# 1-Schematic_simple_slew_limiter.net
KiCad netlist of a schematic drawn in EasyEDA
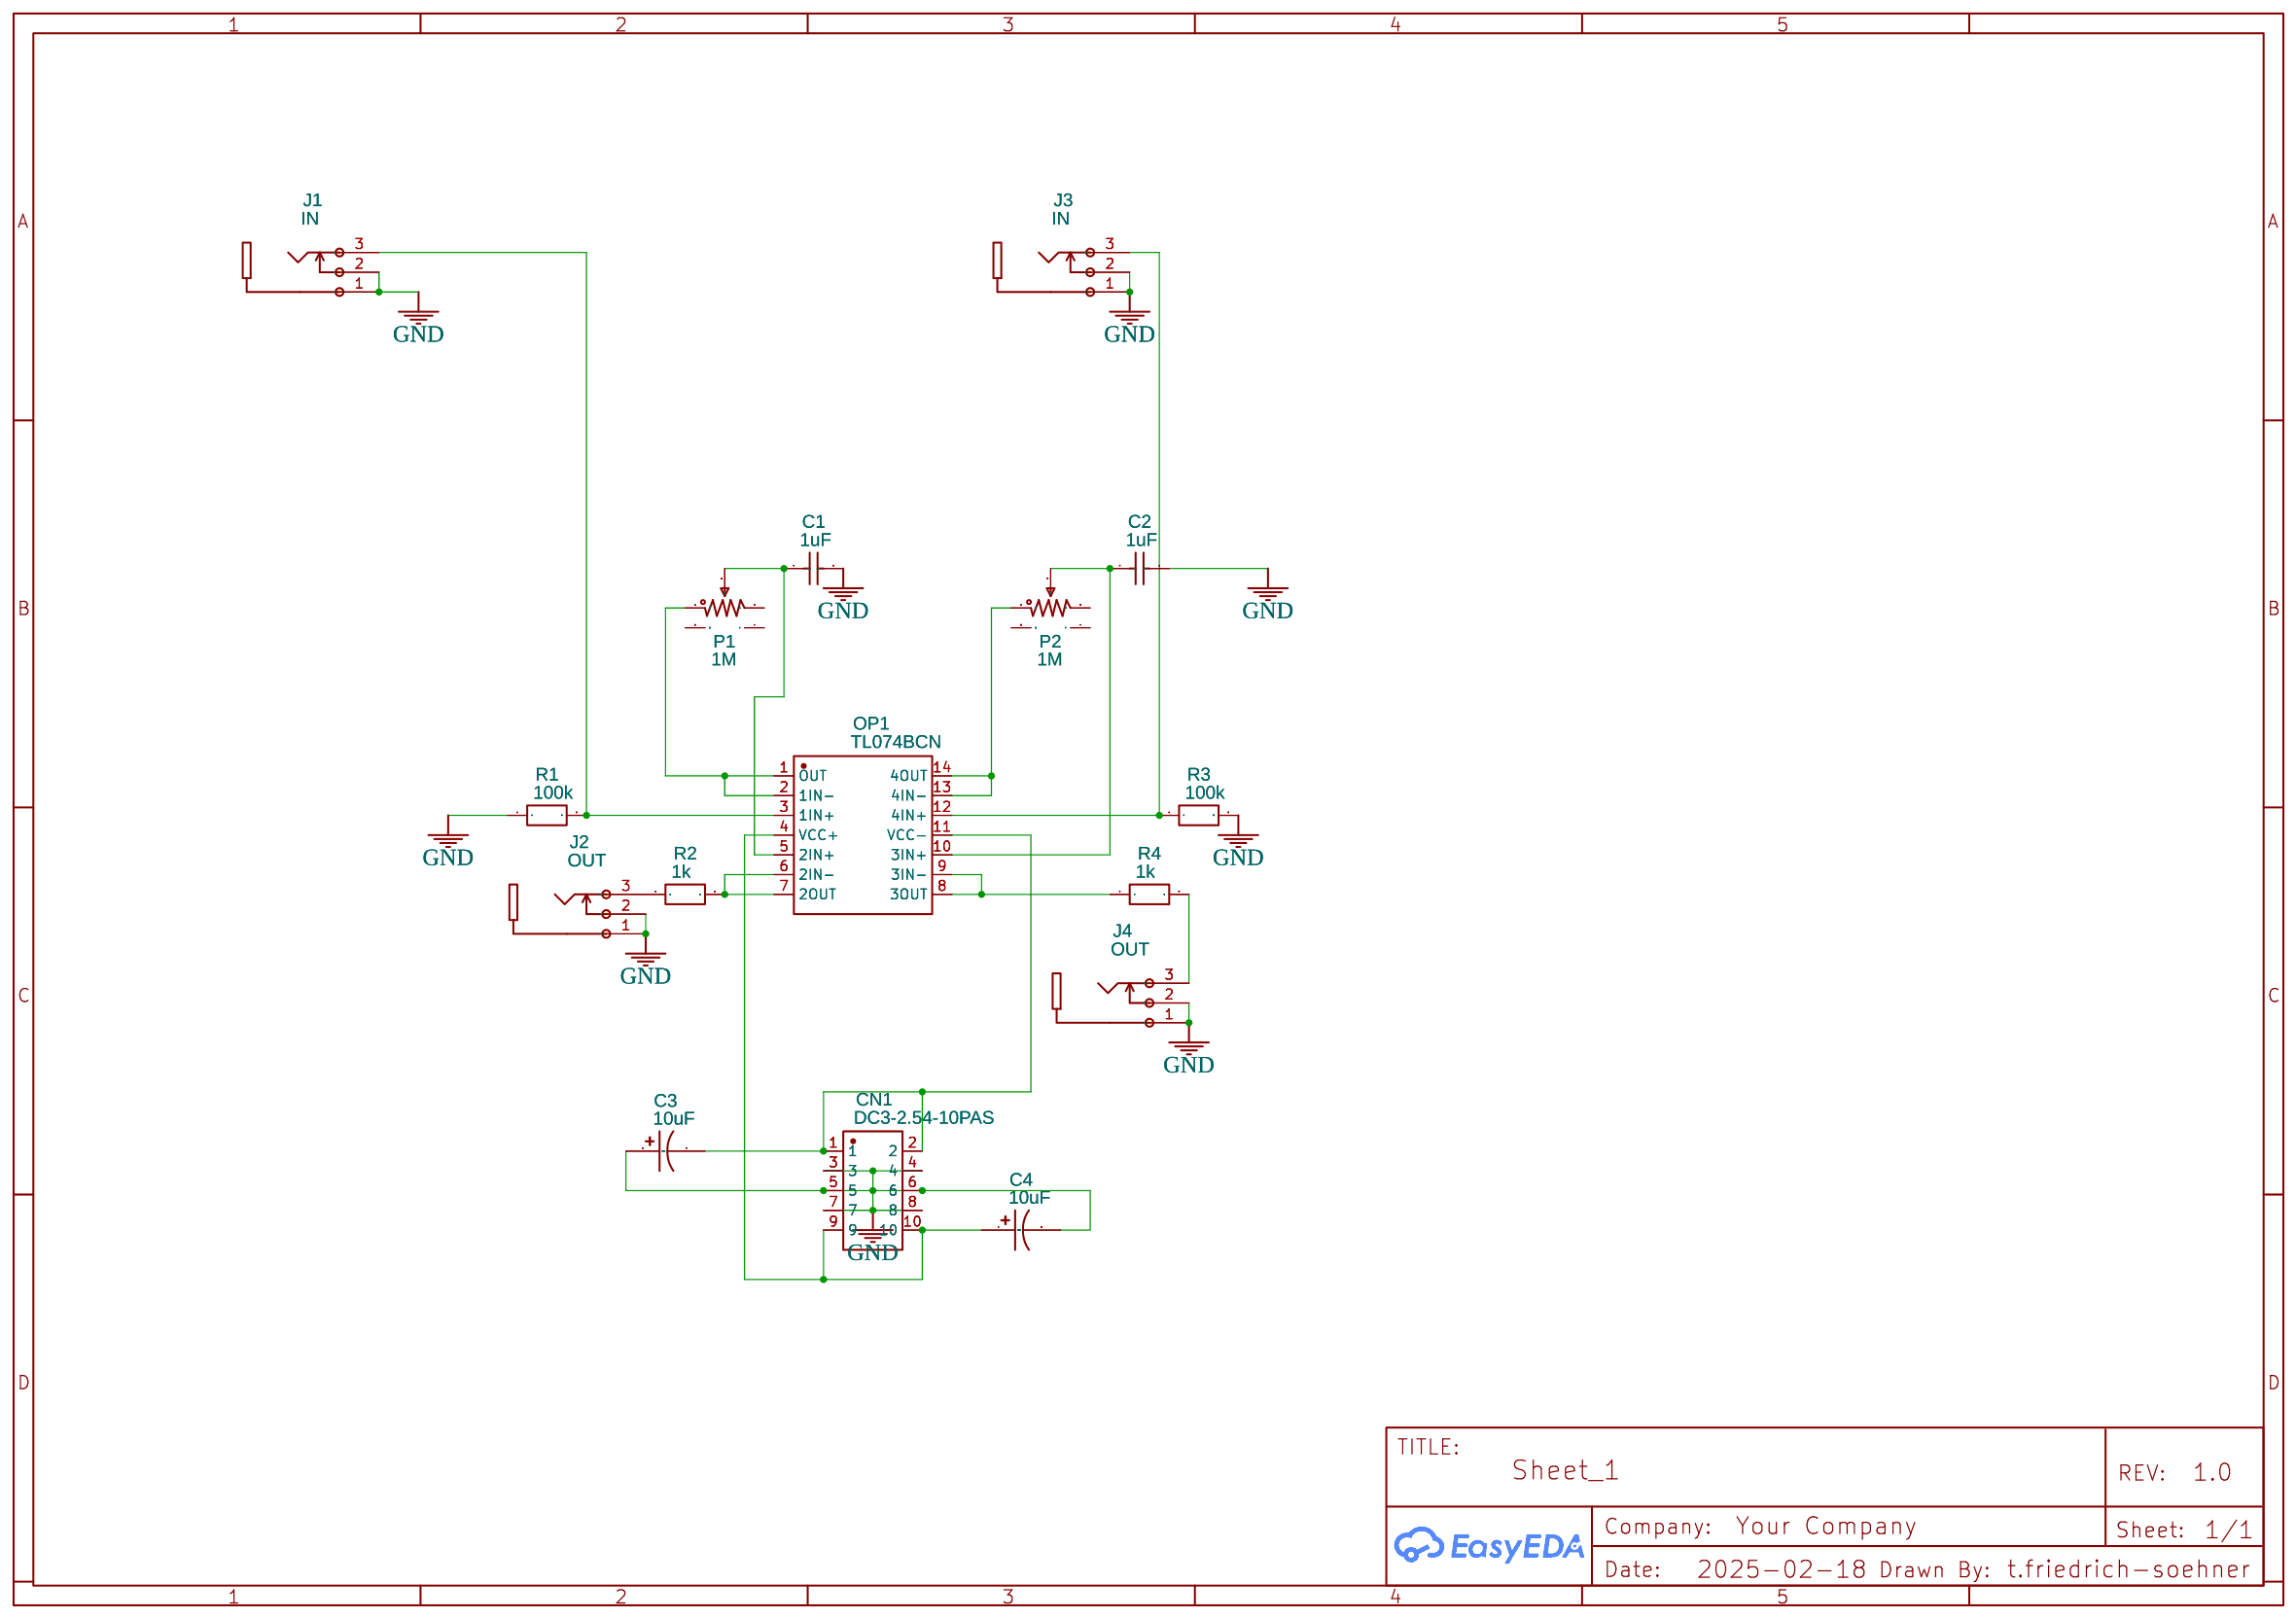
[diagram p0: schematic sheet]

(export (version "E")
  (design (tool "Eeschema 10.0.6"))
  (components
    (comp (ref "C1")
      (value "1uF")
      (fields
        (field (name "Manufacturer Part") "0.22uF 5% 100VCalibration capacitor")
        (field (name "Manufacturer") "ReliaPro")
      )
      (libsource (lib "") (part "0.22uF 5% 100VCalibration capacitor"))
    )
    (comp (ref "C2")
      (value "1uF")
      (fields
        (field (name "Manufacturer Part") "0.22uF 5% 100VCalibration capacitor")
        (field (name "Manufacturer") "ReliaPro")
      )
      (libsource (lib "") (part "0.22uF 5% 100VCalibration capacitor"))
    )
    (comp (ref "C3")
      (value "10uF")
      (fields
        (field (name "Manufacturer Part") "50MS710MEFCTZ5X7")
        (field (name "Manufacturer") "rubycon(红宝石)")
      )
      (libsource (lib "") (part "50MS710MEFCTZ5X7"))
    )
    (comp (ref "C4")
      (value "10uF")
      (fields
        (field (name "Manufacturer Part") "50MS710MEFCTZ5X7")
        (field (name "Manufacturer") "rubycon(红宝石)")
      )
      (libsource (lib "") (part "50MS710MEFCTZ5X7"))
    )
    (comp (ref "CN1")
      (value "DC3-2.54-10PAS")
      (fields (field (name "Manufacturer") "ZHOURI(洲日)"))
      (libsource (lib "") (part "DC3-2.54-10PAS"))
    )
    (comp (ref "J1") (value "IN") (libsource (lib "") (part "PJ-301M")))
    (comp (ref "J2") (value "OUT") (libsource (lib "") (part "PJ-301M")))
    (comp (ref "J3") (value "IN") (libsource (lib "") (part "PJ-301M")))
    (comp (ref "J4") (value "OUT") (libsource (lib "") (part "PJ-301M")))
    (comp (ref "OP1")
      (value "TL074BCN")
      (fields (field (name "Manufacturer") "TI(德州仪器)"))
      (libsource (lib "") (part "TL074BCN"))
    )
    (comp (ref "P1")
      (value "1M")
      (fields
        (field (name "Manufacturer Part") "RK09K1130081")
        (field (name "Manufacturer") "ALPSALPINE(阿尔卑斯阿尔派)")
      )
      (libsource (lib "") (part "RK09K1130081"))
    )
    (comp (ref "P2")
      (value "1M")
      (fields
        (field (name "Manufacturer Part") "RK09K1130081")
        (field (name "Manufacturer") "ALPSALPINE(阿尔卑斯阿尔派)")
      )
      (libsource (lib "") (part "RK09K1130081"))
    )
    (comp (ref "R1") (value "100k") (libsource (lib "") (part "Res_AXIAL-0.4(1/4W)_US")))
    (comp (ref "R2") (value "1k") (libsource (lib "") (part "Res_AXIAL-0.4(1/4W)_US")))
    (comp (ref "R3") (value "100k") (libsource (lib "") (part "Res_AXIAL-0.4(1/4W)_US")))
    (comp (ref "R4") (value "1k") (libsource (lib "") (part "Res_AXIAL-0.4(1/4W)_US")))
  )
  (nets
    (net (code "1") (name "GND") (class "Default")
      (node (ref "C1") (pin "2") (pinfunction "2_2") (pintype "input"))
      (node (ref "C2") (pin "2") (pinfunction "2_2") (pintype "input"))
      (node (ref "C3") (pin "1") (pinfunction "1_1") (pintype "unspecified"))
      (node (ref "C4") (pin "2") (pinfunction "2_2") (pintype "unspecified"))
      (node (ref "CN1") (pin "3") (pinfunction "3_3") (pintype "unspecified"))
      (node (ref "CN1") (pin "4") (pinfunction "4_4") (pintype "unspecified"))
      (node (ref "CN1") (pin "5") (pinfunction "5_5") (pintype "unspecified"))
      (node (ref "CN1") (pin "6") (pinfunction "6_6") (pintype "unspecified"))
      (node (ref "CN1") (pin "7") (pinfunction "7_7") (pintype "unspecified"))
      (node (ref "CN1") (pin "8") (pinfunction "8_8") (pintype "unspecified"))
      (node (ref "J1") (pin "1") (pinfunction "1_1") (pintype "unspecified"))
      (node (ref "J1") (pin "2") (pinfunction "2_2") (pintype "unspecified"))
      (node (ref "J2") (pin "1") (pinfunction "1_1") (pintype "unspecified"))
      (node (ref "J2") (pin "2") (pinfunction "2_2") (pintype "unspecified"))
      (node (ref "J3") (pin "1") (pinfunction "1_1") (pintype "unspecified"))
      (node (ref "J3") (pin "2") (pinfunction "2_2") (pintype "unspecified"))
      (node (ref "J4") (pin "1") (pinfunction "1_1") (pintype "unspecified"))
      (node (ref "J4") (pin "2") (pinfunction "2_2") (pintype "unspecified"))
      (node (ref "R1") (pin "1") (pinfunction "1_1") (pintype "unspecified"))
      (node (ref "R3") (pin "2") (pinfunction "2_2") (pintype "unspecified"))
    )
    (net (code "2") (name "Net-(J2-Pad3)") (class "Default")
      (node (ref "J2") (pin "3") (pinfunction "3_3") (pintype "unspecified"))
      (node (ref "R2") (pin "1") (pinfunction "1_1") (pintype "unspecified"))
    )
    (net (code "3") (name "Net-(J4-Pad3)") (class "Default")
      (node (ref "J4") (pin "3") (pinfunction "3_3") (pintype "unspecified"))
      (node (ref "R4") (pin "2") (pinfunction "2_2") (pintype "unspecified"))
    )
    (net (code "4") (name "Net-(OP1-1IN+)") (class "Default")
      (node (ref "J1") (pin "3") (pinfunction "3_3") (pintype "unspecified"))
      (node (ref "OP1") (pin "3") (pinfunction "1IN+_3") (pintype "unspecified"))
      (node (ref "R1") (pin "2") (pinfunction "2_2") (pintype "unspecified"))
    )
    (net (code "5") (name "Net-(OP1-1IN-)") (class "Default")
      (node (ref "OP1") (pin "1") (pinfunction "OUT_1") (pintype "unspecified"))
      (node (ref "OP1") (pin "2") (pinfunction "1IN-_2") (pintype "unspecified"))
      (node (ref "P1") (pin "1") (pinfunction "1_1") (pintype "unspecified"))
    )
    (net (code "6") (name "Net-(OP1-2IN+)") (class "Default")
      (node (ref "C1") (pin "1") (pinfunction "1_1") (pintype "input"))
      (node (ref "OP1") (pin "5") (pinfunction "2IN+_5") (pintype "unspecified"))
      (node (ref "P1") (pin "2") (pinfunction "2_2") (pintype "unspecified"))
    )
    (net (code "7") (name "Net-(OP1-2IN-)") (class "Default")
      (node (ref "OP1") (pin "6") (pinfunction "2IN-_6") (pintype "unspecified"))
      (node (ref "OP1") (pin "7") (pinfunction "2OUT_7") (pintype "unspecified"))
      (node (ref "R2") (pin "2") (pinfunction "2_2") (pintype "unspecified"))
    )
    (net (code "8") (name "Net-(OP1-3IN+)") (class "Default")
      (node (ref "C2") (pin "1") (pinfunction "1_1") (pintype "input"))
      (node (ref "OP1") (pin "10") (pinfunction "3IN+_10") (pintype "unspecified"))
      (node (ref "P2") (pin "2") (pinfunction "2_2") (pintype "unspecified"))
    )
    (net (code "9") (name "Net-(OP1-3IN-)") (class "Default")
      (node (ref "OP1") (pin "8") (pinfunction "3OUT_8") (pintype "unspecified"))
      (node (ref "OP1") (pin "9") (pinfunction "3IN-_9") (pintype "unspecified"))
      (node (ref "R4") (pin "1") (pinfunction "1_1") (pintype "unspecified"))
    )
    (net (code "10") (name "Net-(OP1-4IN+)") (class "Default")
      (node (ref "J3") (pin "3") (pinfunction "3_3") (pintype "unspecified"))
      (node (ref "OP1") (pin "12") (pinfunction "4IN+_12") (pintype "unspecified"))
      (node (ref "R3") (pin "1") (pinfunction "1_1") (pintype "unspecified"))
    )
    (net (code "11") (name "Net-(OP1-4IN-)") (class "Default")
      (node (ref "OP1") (pin "13") (pinfunction "4IN-_13") (pintype "unspecified"))
      (node (ref "OP1") (pin "14") (pinfunction "4OUT_14") (pintype "unspecified"))
      (node (ref "P2") (pin "1") (pinfunction "1_1") (pintype "unspecified"))
    )
    (net (code "12") (name "Net-(OP1-VCC+)") (class "Default")
      (node (ref "C4") (pin "1") (pinfunction "1_1") (pintype "unspecified"))
      (node (ref "CN1") (pin "10") (pinfunction "10_10") (pintype "unspecified"))
      (node (ref "CN1") (pin "9") (pinfunction "9_9") (pintype "unspecified"))
      (node (ref "OP1") (pin "4") (pinfunction "VCC+_4") (pintype "unspecified"))
    )
    (net (code "13") (name "Net-(OP1-VCC-)") (class "Default")
      (node (ref "C3") (pin "2") (pinfunction "2_2") (pintype "unspecified"))
      (node (ref "CN1") (pin "1") (pinfunction "1_1") (pintype "unspecified"))
      (node (ref "CN1") (pin "2") (pinfunction "2_2") (pintype "unspecified"))
      (node (ref "OP1") (pin "11") (pinfunction "VCC-_11") (pintype "unspecified"))
    )
    (net (code "14") (name "unconnected-(P1-Pad3)") (class "Default")
      (node (ref "P1") (pin "3") (pinfunction "3_3") (pintype "unspecified"))
    )
    (net (code "15") (name "unconnected-(P1-Pad4)") (class "Default")
      (node (ref "P1") (pin "4") (pinfunction "4_4") (pintype "unspecified"))
    )
    (net (code "16") (name "unconnected-(P1-Pad5)") (class "Default")
      (node (ref "P1") (pin "5") (pinfunction "5_5") (pintype "unspecified"))
    )
    (net (code "17") (name "unconnected-(P2-Pad3)") (class "Default")
      (node (ref "P2") (pin "3") (pinfunction "3_3") (pintype "unspecified"))
    )
    (net (code "18") (name "unconnected-(P2-Pad4)") (class "Default")
      (node (ref "P2") (pin "4") (pinfunction "4_4") (pintype "unspecified"))
    )
    (net (code "19") (name "unconnected-(P2-Pad5)") (class "Default")
      (node (ref "P2") (pin "5") (pinfunction "5_5") (pintype "unspecified"))
    )
  )
)
